# uCurrent.net
KiCad netlist of a schematic drawn in EAGLE
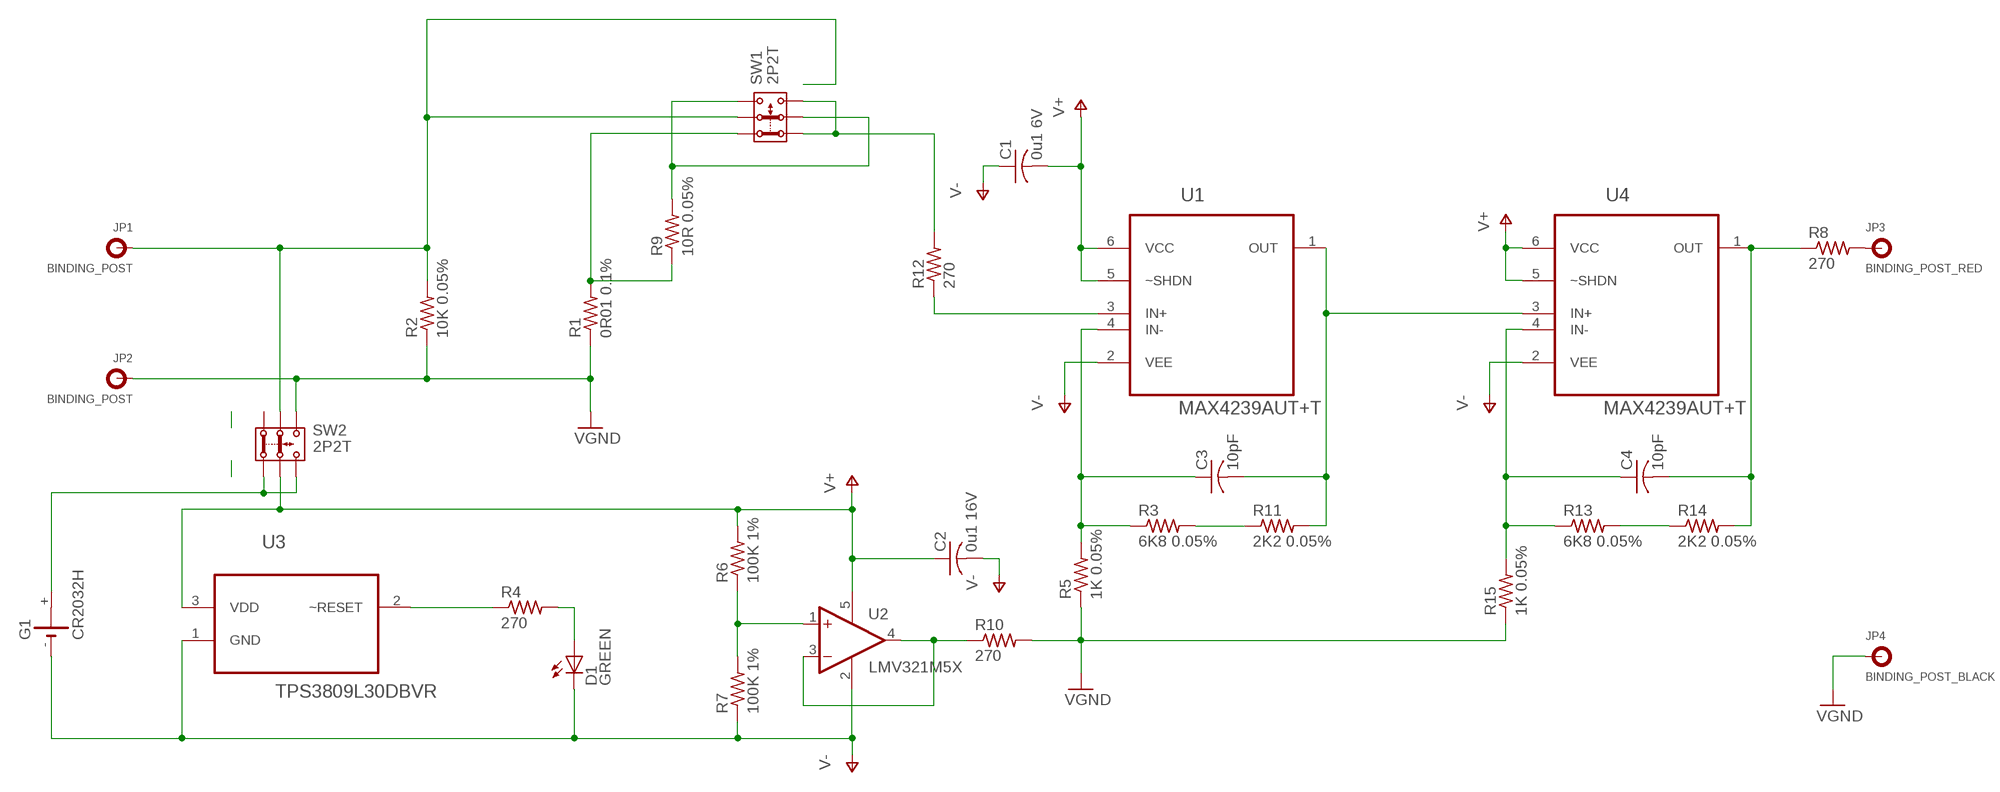
[diagram p0: schematic, sheet 1]

(export (version "E")
  (design (tool "Eeschema 10.0.6"))
  (components
    (comp (ref "C1")
      (value "0u1 6V")
      (footprint "eagle-import:C0402")
      (libsource (lib "eagle-import") (part "C-USC0402"))
    )
    (comp (ref "C2")
      (value "0u1 16V")
      (footprint "eagle-import:C0402")
      (libsource (lib "eagle-import") (part "C-USC0402"))
    )
    (comp (ref "C3")
      (value "10pF")
      (footprint "eagle-import:C0402")
      (libsource (lib "eagle-import") (part "C-USC0402"))
    )
    (comp (ref "C4")
      (value "10pF")
      (footprint "eagle-import:C0402")
      (libsource (lib "eagle-import") (part "C-USC0402"))
    )
    (comp (ref "D1")
      (value "GREEN")
      (footprint "eagle-import:LED3MM")
      (libsource (lib "eagle-import") (part "LED3MM"))
    )
    (comp (ref "G1")
      (value "CR2032H")
      (footprint "eagle-import:CR2032H")
      (libsource (lib "eagle-import") (part "CR2032H"))
    )
    (comp (ref "JP1")
      (value "BINDING_POST")
      (footprint "eagle-import:BINDING_POST")
      (libsource (lib "eagle-import") (part "BINDING_POST"))
    )
    (comp (ref "JP2")
      (value "BINDING_POST")
      (footprint "eagle-import:BINDING_POST")
      (libsource (lib "eagle-import") (part "BINDING_POST"))
    )
    (comp (ref "JP3")
      (value "BINDING_POST_RED")
      (footprint "eagle-import:BINDING_POST")
      (libsource (lib "eagle-import") (part "BINDING_POST"))
    )
    (comp (ref "JP4")
      (value "BINDING_POST_BLACK")
      (footprint "eagle-import:BINDING_POST")
      (libsource (lib "eagle-import") (part "BINDING_POST"))
    )
    (comp (ref "R1")
      (value "0R01 0.1%")
      (footprint "eagle-import:R0402")
      (libsource (lib "eagle-import") (part "R-US_R0402"))
    )
    (comp (ref "R2")
      (value "10K 0.05%")
      (footprint "eagle-import:R0402")
      (libsource (lib "eagle-import") (part "R-US_R0402"))
    )
    (comp (ref "R3")
      (value "6K8 0.05%")
      (footprint "eagle-import:R0402")
      (libsource (lib "eagle-import") (part "R-US_R0402"))
    )
    (comp (ref "R4")
      (value "270")
      (footprint "eagle-import:R0402")
      (libsource (lib "eagle-import") (part "R-US_R0402"))
    )
    (comp (ref "R5")
      (value "1K 0.05%")
      (footprint "eagle-import:R0402")
      (libsource (lib "eagle-import") (part "R-US_R0402"))
    )
    (comp (ref "R6")
      (value "100K 1%")
      (footprint "eagle-import:R0402")
      (libsource (lib "eagle-import") (part "R-US_R0402"))
    )
    (comp (ref "R7")
      (value "100K 1%")
      (footprint "eagle-import:R0402")
      (libsource (lib "eagle-import") (part "R-US_R0402"))
    )
    (comp (ref "R8")
      (value "270")
      (footprint "eagle-import:R0402")
      (libsource (lib "eagle-import") (part "R-US_R0402"))
    )
    (comp (ref "R9")
      (value "10R 0.05%")
      (footprint "eagle-import:R0402")
      (libsource (lib "eagle-import") (part "R-US_R0402"))
    )
    (comp (ref "R10")
      (value "270")
      (footprint "eagle-import:R0402")
      (libsource (lib "eagle-import") (part "R-US_R0402"))
    )
    (comp (ref "R11")
      (value "2K2 0.05%")
      (footprint "eagle-import:R0402")
      (libsource (lib "eagle-import") (part "R-US_R0402"))
    )
    (comp (ref "R12")
      (value "270")
      (footprint "eagle-import:R0402")
      (libsource (lib "eagle-import") (part "R-US_R0402"))
    )
    (comp (ref "R13")
      (value "6K8 0.05%")
      (footprint "eagle-import:R0402")
      (libsource (lib "eagle-import") (part "R-US_R0402"))
    )
    (comp (ref "R14")
      (value "2K2 0.05%")
      (footprint "eagle-import:R0402")
      (libsource (lib "eagle-import") (part "R-US_R0402"))
    )
    (comp (ref "R15")
      (value "1K 0.05%")
      (footprint "eagle-import:R0402")
      (libsource (lib "eagle-import") (part "R-US_R0402"))
    )
    (comp (ref "SW1")
      (value "2P2T")
      (footprint "eagle-import:2P2T")
      (libsource (lib "eagle-import") (part "2P2T"))
    )
    (comp (ref "SW2")
      (value "2P2T")
      (footprint "eagle-import:2P2T")
      (libsource (lib "eagle-import") (part "2P2T"))
    )
    (comp (ref "U1")
      (value "MAX4239AUT+T")
      (footprint "eagle-import:SOT95P280X145-6N")
      (fields (field (name "MPN") "MAX4237EUT+T"))
      (libsource (lib "eagle-import") (part "MAX4237EUT+T"))
    )
    (comp (ref "U2")
      (value "LMV321M5X")
      (footprint "eagle-import:SOT23-5")
      (libsource (lib "eagle-import") (part "LMV321?M5X"))
    )
    (comp (ref "U3")
      (value "TPS3809L30DBVR")
      (footprint "eagle-import:SOT95P280X145-3N")
      (libsource (lib "eagle-import") (part "TPS3809L30DBVR"))
    )
    (comp (ref "U4")
      (value "MAX4239AUT+T")
      (footprint "eagle-import:SOT95P280X145-6N")
      (fields (field (name "MPN") "MAX4237EUT+T"))
      (libsource (lib "eagle-import") (part "MAX4237EUT+T"))
    )
  )
  (nets
    (net (code "1") (name "Net-(D1-PadA)") (class "Default")
      (node (ref "D1") (pin "A") (pinfunction "A_A") (pintype "passive"))
      (node (ref "R4") (pin "2") (pinfunction "2_2") (pintype "passive"))
    )
    (net (code "2") (name "Net-(G1-Pad+)") (class "Default")
      (node (ref "G1") (pin "+") (pinfunction "+_+") (pintype "passive"))
      (node (ref "SW2") (pin "1.2") (pinfunction "1.2_1.2") (pintype "passive"))
      (node (ref "SW2") (pin "3.2") (pinfunction "3.2_3.2") (pintype "passive"))
    )
    (net (code "3") (name "Net-(JP1-PadP$1)") (class "Default")
      (node (ref "JP1") (pin "P$1") (pinfunction "P$1_P$1") (pintype "bidirectional"))
      (node (ref "R2") (pin "2") (pinfunction "2_2") (pintype "passive"))
      (node (ref "SW1") (pin "2.1") (pinfunction "2.1_2.1") (pintype "passive"))
      (node (ref "SW2") (pin "2.1") (pinfunction "2.1_2.1") (pintype "passive"))
    )
    (net (code "4") (name "Net-(JP3-PadP$1)") (class "Default")
      (node (ref "JP3") (pin "P$1") (pinfunction "P$1_P$1") (pintype "bidirectional"))
      (node (ref "R8") (pin "2") (pinfunction "2_2") (pintype "passive"))
    )
    (net (code "5") (name "Net-(R1-Pad2)") (class "Default")
      (node (ref "R1") (pin "2") (pinfunction "2_2") (pintype "passive"))
      (node (ref "R9") (pin "1") (pinfunction "1_1") (pintype "passive"))
      (node (ref "SW1") (pin "1.1") (pinfunction "1.1_1.1") (pintype "passive"))
    )
    (net (code "6") (name "Net-(R9-Pad2)") (class "Default")
      (node (ref "R9") (pin "2") (pinfunction "2_2") (pintype "passive"))
      (node (ref "SW1") (pin "2.2") (pinfunction "2.2_2.2") (pintype "passive"))
      (node (ref "SW1") (pin "3.1") (pinfunction "3.1_3.1") (pintype "passive"))
    )
    (net (code "7") (name "Net-(R11-Pad1)") (class "Default")
      (node (ref "R11") (pin "1") (pinfunction "1_1") (pintype "passive"))
      (node (ref "R3") (pin "2") (pinfunction "2_2") (pintype "passive"))
    )
    (net (code "8") (name "Net-(R12-Pad2)") (class "Default")
      (node (ref "R12") (pin "2") (pinfunction "2_2") (pintype "passive"))
      (node (ref "SW1") (pin "1.2") (pinfunction "1.2_1.2") (pintype "passive"))
      (node (ref "SW1") (pin "3.2") (pinfunction "3.2_3.2") (pintype "passive"))
    )
    (net (code "9") (name "Net-(R13-Pad2)") (class "Default")
      (node (ref "R13") (pin "2") (pinfunction "2_2") (pintype "passive"))
      (node (ref "R14") (pin "1") (pinfunction "1_1") (pintype "passive"))
    )
    (net (code "10") (name "Net-(U1-IN+)") (class "Default")
      (node (ref "R12") (pin "1") (pinfunction "1_1") (pintype "passive"))
      (node (ref "U1") (pin "3") (pinfunction "IN+_3") (pintype "input"))
    )
    (net (code "11") (name "Net-(U1-IN-)") (class "Default")
      (node (ref "C3") (pin "1") (pinfunction "1_1") (pintype "passive"))
      (node (ref "R3") (pin "1") (pinfunction "1_1") (pintype "passive"))
      (node (ref "R5") (pin "2") (pinfunction "2_2") (pintype "passive"))
      (node (ref "U1") (pin "4") (pinfunction "IN-_4") (pintype "input"))
    )
    (net (code "12") (name "Net-(U1-OUT)") (class "Default")
      (node (ref "C3") (pin "2") (pinfunction "2_2") (pintype "passive"))
      (node (ref "R11") (pin "2") (pinfunction "2_2") (pintype "passive"))
      (node (ref "U1") (pin "1") (pinfunction "OUT_1") (pintype "output"))
      (node (ref "U4") (pin "3") (pinfunction "IN+_3") (pintype "input"))
    )
    (net (code "13") (name "Net-(U2-+IN)") (class "Default")
      (node (ref "R6") (pin "1") (pinfunction "1_1") (pintype "passive"))
      (node (ref "R7") (pin "2") (pinfunction "2_2") (pintype "passive"))
      (node (ref "U2") (pin "1") (pinfunction "+IN_1") (pintype "input"))
    )
    (net (code "14") (name "Net-(U2--IN)") (class "Default")
      (node (ref "R10") (pin "1") (pinfunction "1_1") (pintype "passive"))
      (node (ref "U2") (pin "3") (pinfunction "-IN_3") (pintype "input"))
      (node (ref "U2") (pin "4") (pinfunction "OUT_4") (pintype "output"))
    )
    (net (code "15") (name "Net-(U3-~{RESET})") (class "Default")
      (node (ref "R4") (pin "1") (pinfunction "1_1") (pintype "passive"))
      (node (ref "U3") (pin "2") (pinfunction "~{RESET}_2") (pintype "output"))
    )
    (net (code "16") (name "Net-(U4-IN-)") (class "Default")
      (node (ref "C4") (pin "1") (pinfunction "1_1") (pintype "passive"))
      (node (ref "R13") (pin "1") (pinfunction "1_1") (pintype "passive"))
      (node (ref "R15") (pin "2") (pinfunction "2_2") (pintype "passive"))
      (node (ref "U4") (pin "4") (pinfunction "IN-_4") (pintype "input"))
    )
    (net (code "17") (name "Net-(U4-OUT)") (class "Default")
      (node (ref "C4") (pin "2") (pinfunction "2_2") (pintype "passive"))
      (node (ref "R14") (pin "2") (pinfunction "2_2") (pintype "passive"))
      (node (ref "R8") (pin "1") (pinfunction "1_1") (pintype "passive"))
      (node (ref "U4") (pin "1") (pinfunction "OUT_1") (pintype "output"))
    )
    (net (code "18") (name "V+") (class "Default")
      (node (ref "C1") (pin "2") (pinfunction "2_2") (pintype "passive"))
      (node (ref "C2") (pin "1") (pinfunction "1_1") (pintype "passive"))
      (node (ref "R6") (pin "2") (pinfunction "2_2") (pintype "passive"))
      (node (ref "SW2") (pin "2.2") (pinfunction "2.2_2.2") (pintype "passive"))
      (node (ref "U1") (pin "5") (pinfunction "~{SHDN}_5") (pintype "input"))
      (node (ref "U1") (pin "6") (pinfunction "VCC_6") (pintype "power_in"))
      (node (ref "U2") (pin "5") (pinfunction "V+_5") (pintype "power_in"))
      (node (ref "U3") (pin "3") (pinfunction "VDD_3") (pintype "power_in"))
      (node (ref "U4") (pin "5") (pinfunction "~{SHDN}_5") (pintype "input"))
      (node (ref "U4") (pin "6") (pinfunction "VCC_6") (pintype "power_in"))
    )
    (net (code "19") (name "V-") (class "Default")
      (node (ref "C1") (pin "1") (pinfunction "1_1") (pintype "passive"))
      (node (ref "C2") (pin "2") (pinfunction "2_2") (pintype "passive"))
      (node (ref "D1") (pin "K") (pinfunction "C_K") (pintype "passive"))
      (node (ref "G1") (pin "-") (pinfunction "-_-") (pintype "passive"))
      (node (ref "R7") (pin "1") (pinfunction "1_1") (pintype "passive"))
      (node (ref "U1") (pin "2") (pinfunction "VEE_2") (pintype "power_in"))
      (node (ref "U2") (pin "2") (pinfunction "V-_2") (pintype "power_in"))
      (node (ref "U3") (pin "1") (pinfunction "GND_1") (pintype "passive"))
      (node (ref "U4") (pin "2") (pinfunction "VEE_2") (pintype "power_in"))
    )
    (net (code "20") (name "VGND") (class "Default")
      (node (ref "JP2") (pin "P$1") (pinfunction "P$1_P$1") (pintype "bidirectional"))
      (node (ref "JP4") (pin "P$1") (pinfunction "P$1_P$1") (pintype "bidirectional"))
      (node (ref "R1") (pin "1") (pinfunction "1_1") (pintype "passive"))
      (node (ref "R10") (pin "2") (pinfunction "2_2") (pintype "passive"))
      (node (ref "R15") (pin "1") (pinfunction "1_1") (pintype "passive"))
      (node (ref "R2") (pin "1") (pinfunction "1_1") (pintype "passive"))
      (node (ref "R5") (pin "1") (pinfunction "1_1") (pintype "passive"))
      (node (ref "SW2") (pin "3.1") (pinfunction "3.1_3.1") (pintype "passive"))
    )
    (net (code "21") (name "unconnected-(G1-+-Pad+@1)") (class "Default")
      (node (ref "G1") (pin "+@1") (pinfunction "+_+@1") (pintype "passive"))
    )
    (net (code "22") (name "unconnected-(SW2-Pad1.1)") (class "Default")
      (node (ref "SW2") (pin "1.1") (pinfunction "1.1_1.1") (pintype "passive"))
    )
  )
)
